# vp_2019-11b.net
KiCad netlist of a schematic drawn in EAGLE
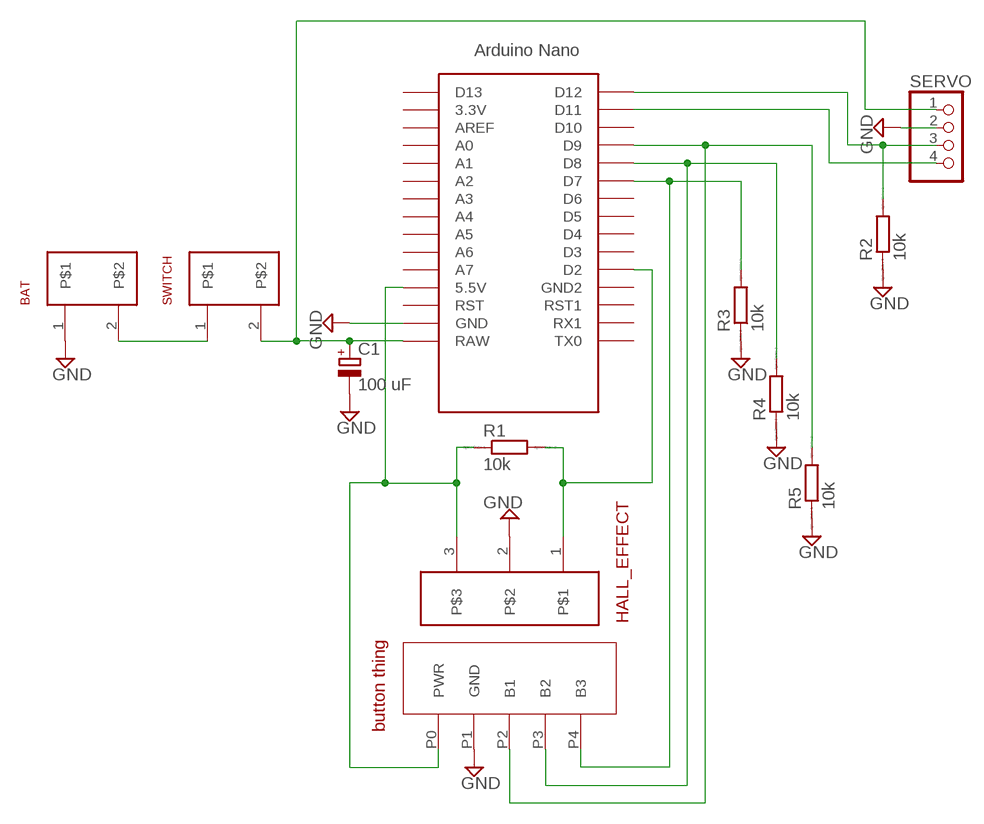
[diagram p0: schematic, sheet 1]

(export (version "E")
  (design (tool "Eeschema 10.0.6"))
  (components
    (comp (ref "BAT")
      (value "TERMINAL_2POS")
      (footprint "eagle-import:TERMINAL_2POS")
      (libsource (lib "eagle-import") (part "TERMINAL_2POS"))
    )
    (comp (ref "BUTTON")
      (value "BUTTON_CRAP")
      (footprint "eagle-import:5PIN")
      (libsource (lib "eagle-import") (part "BUTTON_CRAP"))
    )
    (comp (ref "C1")
      (value "100 uF")
      (footprint "eagle-import:E2-5")
      (libsource (lib "eagle-import") (part "CPOL-EUE2-5"))
    )
    (comp (ref "HALL_EFFECT")
      (value "TERMINAL_3POS")
      (footprint "eagle-import:TERMINAL_3POS")
      (libsource (lib "eagle-import") (part "TERMINAL_3POS"))
    )
    (comp (ref "R1")
      (value "10k")
      (footprint "eagle-import:R0603")
      (libsource (lib "eagle-import") (part "RR0603"))
    )
    (comp (ref "R2")
      (value "10k")
      (footprint "eagle-import:R0603")
      (libsource (lib "eagle-import") (part "RR0603"))
    )
    (comp (ref "R3")
      (value "10k")
      (footprint "eagle-import:R0603")
      (libsource (lib "eagle-import") (part "RR0603"))
    )
    (comp (ref "R4")
      (value "10k")
      (footprint "eagle-import:R0603")
      (libsource (lib "eagle-import") (part "RR0603"))
    )
    (comp (ref "R5")
      (value "10k")
      (footprint "eagle-import:R0603")
      (libsource (lib "eagle-import") (part "RR0603"))
    )
    (comp (ref "SERVO")
      (value "PINHD-1X4")
      (footprint "eagle-import:1X04")
      (libsource (lib "eagle-import") (part "PINHD-1X4"))
    )
    (comp (ref "SWITCH")
      (value "TERMINAL_2POS")
      (footprint "eagle-import:TERMINAL_2POS")
      (libsource (lib "eagle-import") (part "TERMINAL_2POS"))
    )
    (comp (ref "U$1")
      (value "NANO")
      (footprint "eagle-import:NANO")
      (libsource (lib "eagle-import") (part "NANO"))
    )
  )
  (nets
    (net (code "1") (name "GND") (class "Default")
      (node (ref "BAT") (pin "1") (pinfunction "P$1_1") (pintype "bidirectional"))
      (node (ref "BUTTON") (pin "P1") (pinfunction "GND_P1") (pintype "bidirectional"))
      (node (ref "C1") (pin "-") (pinfunction "-_-") (pintype "passive"))
      (node (ref "HALL_EFFECT") (pin "2") (pinfunction "P$2_2") (pintype "bidirectional"))
      (node (ref "R2") (pin "1") (pinfunction "1_1") (pintype "passive"))
      (node (ref "R3") (pin "1") (pinfunction "1_1") (pintype "passive"))
      (node (ref "R4") (pin "1") (pinfunction "1_1") (pintype "passive"))
      (node (ref "R5") (pin "1") (pinfunction "1_1") (pintype "passive"))
      (node (ref "SERVO") (pin "2") (pinfunction "2_2") (pintype "passive"))
      (node (ref "U$1") (pin "GND") (pinfunction "GND_GND") (pintype "bidirectional"))
    )
    (net (code "2") (name "Net-(BAT-P$2)") (class "Default")
      (node (ref "BAT") (pin "2") (pinfunction "P$2_2") (pintype "bidirectional"))
      (node (ref "SWITCH") (pin "1") (pinfunction "P$1_1") (pintype "bidirectional"))
    )
    (net (code "3") (name "Net-(BUTTON-B1)") (class "Default")
      (node (ref "BUTTON") (pin "P2") (pinfunction "B1_P2") (pintype "bidirectional"))
      (node (ref "R5") (pin "2") (pinfunction "2_2") (pintype "passive"))
      (node (ref "U$1") (pin "D9") (pinfunction "D9_D9") (pintype "bidirectional"))
    )
    (net (code "4") (name "Net-(BUTTON-B2)") (class "Default")
      (node (ref "BUTTON") (pin "P3") (pinfunction "B2_P3") (pintype "bidirectional"))
      (node (ref "R4") (pin "2") (pinfunction "2_2") (pintype "passive"))
      (node (ref "U$1") (pin "D8") (pinfunction "D8_D8") (pintype "bidirectional"))
    )
    (net (code "5") (name "Net-(BUTTON-B3)") (class "Default")
      (node (ref "BUTTON") (pin "P4") (pinfunction "B3_P4") (pintype "bidirectional"))
      (node (ref "R3") (pin "2") (pinfunction "2_2") (pintype "passive"))
      (node (ref "U$1") (pin "D7") (pinfunction "D7_D7") (pintype "bidirectional"))
    )
    (net (code "6") (name "Net-(BUTTON-PWR)") (class "Default")
      (node (ref "BUTTON") (pin "P0") (pinfunction "PWR_P0") (pintype "bidirectional"))
      (node (ref "HALL_EFFECT") (pin "3") (pinfunction "P$3_3") (pintype "bidirectional"))
      (node (ref "R1") (pin "1") (pinfunction "1_1") (pintype "passive"))
      (node (ref "U$1") (pin "5V") (pinfunction "5.5V_5V") (pintype "bidirectional"))
    )
    (net (code "7") (name "Net-(HALL_EFFECT-P$1)") (class "Default")
      (node (ref "HALL_EFFECT") (pin "1") (pinfunction "P$1_1") (pintype "bidirectional"))
      (node (ref "R1") (pin "2") (pinfunction "2_2") (pintype "passive"))
      (node (ref "U$1") (pin "D2") (pinfunction "D2_D2") (pintype "bidirectional"))
    )
    (net (code "8") (name "Net-(R2-Pad2)") (class "Default")
      (node (ref "R2") (pin "2") (pinfunction "2_2") (pintype "passive"))
      (node (ref "SERVO") (pin "3") (pinfunction "3_3") (pintype "passive"))
      (node (ref "U$1") (pin "D12") (pinfunction "D12_D12") (pintype "bidirectional"))
    )
    (net (code "9") (name "Net-(SERVO-Pad4)") (class "Default")
      (node (ref "SERVO") (pin "4") (pinfunction "4_4") (pintype "passive"))
      (node (ref "U$1") (pin "D11") (pinfunction "D11_D11") (pintype "bidirectional"))
    )
    (net (code "10") (name "Net-(SWITCH-P$2)") (class "Default")
      (node (ref "C1") (pin "+") (pinfunction "+_+") (pintype "passive"))
      (node (ref "SERVO") (pin "1") (pinfunction "1_1") (pintype "passive"))
      (node (ref "SWITCH") (pin "2") (pinfunction "P$2_2") (pintype "bidirectional"))
      (node (ref "U$1") (pin "RAW") (pinfunction "RAW_RAW") (pintype "bidirectional"))
    )
    (net (code "11") (name "unconnected-(U$1-GND2-PadGND1)") (class "Default")
      (node (ref "U$1") (pin "GND1") (pinfunction "GND2_GND1") (pintype "bidirectional"))
    )
    (net (code "12") (name "unconnected-(U$1-Pad3.3V)") (class "Default")
      (node (ref "U$1") (pin "3.3V") (pinfunction "3.3V_3.3V") (pintype "bidirectional"))
    )
    (net (code "13") (name "unconnected-(U$1-PadA0)") (class "Default")
      (node (ref "U$1") (pin "A0") (pinfunction "A0_A0") (pintype "bidirectional"))
    )
    (net (code "14") (name "unconnected-(U$1-PadA1)") (class "Default")
      (node (ref "U$1") (pin "A1") (pinfunction "A1_A1") (pintype "bidirectional"))
    )
    (net (code "15") (name "unconnected-(U$1-PadA2)") (class "Default")
      (node (ref "U$1") (pin "A2") (pinfunction "A2_A2") (pintype "bidirectional"))
    )
    (net (code "16") (name "unconnected-(U$1-PadA3)") (class "Default")
      (node (ref "U$1") (pin "A3") (pinfunction "A3_A3") (pintype "bidirectional"))
    )
    (net (code "17") (name "unconnected-(U$1-PadA4)") (class "Default")
      (node (ref "U$1") (pin "A4") (pinfunction "A4_A4") (pintype "bidirectional"))
    )
    (net (code "18") (name "unconnected-(U$1-PadA5)") (class "Default")
      (node (ref "U$1") (pin "A5") (pinfunction "A5_A5") (pintype "bidirectional"))
    )
    (net (code "19") (name "unconnected-(U$1-PadA6)") (class "Default")
      (node (ref "U$1") (pin "A6") (pinfunction "A6_A6") (pintype "bidirectional"))
    )
    (net (code "20") (name "unconnected-(U$1-PadA7)") (class "Default")
      (node (ref "U$1") (pin "A7") (pinfunction "A7_A7") (pintype "bidirectional"))
    )
    (net (code "21") (name "unconnected-(U$1-PadAREF)") (class "Default")
      (node (ref "U$1") (pin "AREF") (pinfunction "AREF_AREF") (pintype "bidirectional"))
    )
    (net (code "22") (name "unconnected-(U$1-PadD3)") (class "Default")
      (node (ref "U$1") (pin "D3") (pinfunction "D3_D3") (pintype "bidirectional"))
    )
    (net (code "23") (name "unconnected-(U$1-PadD4)") (class "Default")
      (node (ref "U$1") (pin "D4") (pinfunction "D4_D4") (pintype "bidirectional"))
    )
    (net (code "24") (name "unconnected-(U$1-PadD5)") (class "Default")
      (node (ref "U$1") (pin "D5") (pinfunction "D5_D5") (pintype "bidirectional"))
    )
    (net (code "25") (name "unconnected-(U$1-PadD6)") (class "Default")
      (node (ref "U$1") (pin "D6") (pinfunction "D6_D6") (pintype "bidirectional"))
    )
    (net (code "26") (name "unconnected-(U$1-PadD10)") (class "Default")
      (node (ref "U$1") (pin "D10") (pinfunction "D10_D10") (pintype "bidirectional"))
    )
    (net (code "27") (name "unconnected-(U$1-PadD13)") (class "Default")
      (node (ref "U$1") (pin "D13") (pinfunction "D13_D13") (pintype "bidirectional"))
    )
    (net (code "28") (name "unconnected-(U$1-PadICSP1)") (class "Default")
      (node (ref "U$1") (pin "ICSP1") (pinfunction "ICSP1_ICSP1") (pintype "bidirectional"))
    )
    (net (code "29") (name "unconnected-(U$1-PadICSP2)") (class "Default")
      (node (ref "U$1") (pin "ICSP2") (pinfunction "ICSP2_ICSP2") (pintype "bidirectional"))
    )
    (net (code "30") (name "unconnected-(U$1-PadICSP3)") (class "Default")
      (node (ref "U$1") (pin "ICSP3") (pinfunction "ICSP3_ICSP3") (pintype "bidirectional"))
    )
    (net (code "31") (name "unconnected-(U$1-PadICSP4)") (class "Default")
      (node (ref "U$1") (pin "ICSP4") (pinfunction "ICSP4_ICSP4") (pintype "bidirectional"))
    )
    (net (code "32") (name "unconnected-(U$1-PadICSP5)") (class "Default")
      (node (ref "U$1") (pin "ICSP5") (pinfunction "ICSP5_ICSP5") (pintype "bidirectional"))
    )
    (net (code "33") (name "unconnected-(U$1-PadICSP6)") (class "Default")
      (node (ref "U$1") (pin "ICSP6") (pinfunction "ICSP6_ICSP6") (pintype "bidirectional"))
    )
    (net (code "34") (name "unconnected-(U$1-PadRST)") (class "Default")
      (node (ref "U$1") (pin "RST") (pinfunction "RST_RST") (pintype "bidirectional"))
    )
    (net (code "35") (name "unconnected-(U$1-PadRST1)") (class "Default")
      (node (ref "U$1") (pin "RST1") (pinfunction "RST1_RST1") (pintype "bidirectional"))
    )
    (net (code "36") (name "unconnected-(U$1-PadRX1)") (class "Default")
      (node (ref "U$1") (pin "RX1") (pinfunction "RX1_RX1") (pintype "bidirectional"))
    )
    (net (code "37") (name "unconnected-(U$1-PadTX0)") (class "Default")
      (node (ref "U$1") (pin "TX0") (pinfunction "TX0_TX0") (pintype "bidirectional"))
    )
  )
)
